# ISO_CAN_Modul.net
KiCad netlist of a schematic drawn in EAGLE
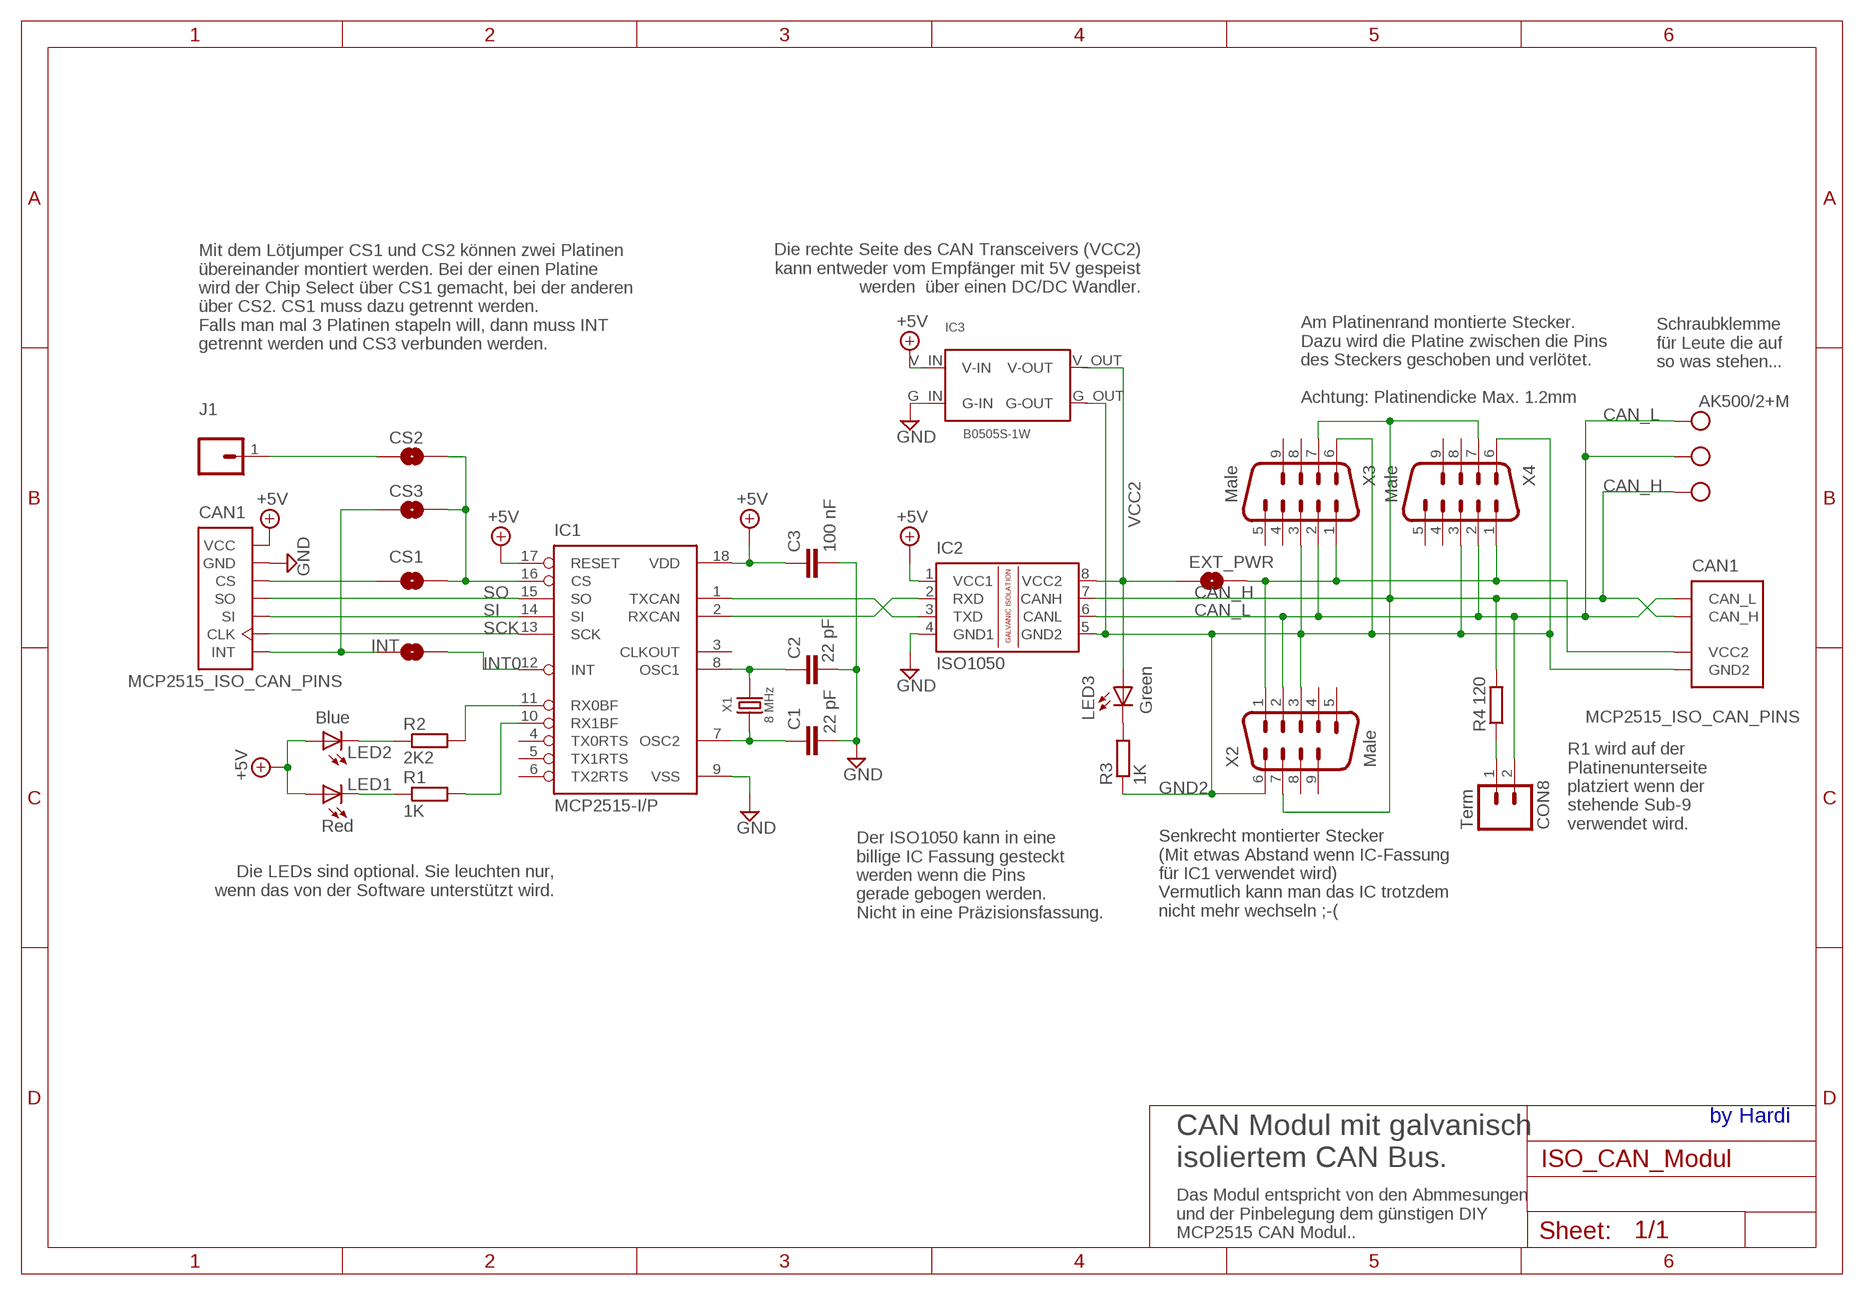
[diagram p0: schematic, sheet 1]

(export (version "E")
  (design (tool "Eeschema 10.0.6"))
  (components
    (comp (ref "C1")
      (value "22 pF")
      (footprint "eagle-import:C2.5-2")
      (libsource (lib "eagle-import") (part "C2.5/2"))
    )
    (comp (ref "C2")
      (value "22 pF")
      (footprint "eagle-import:C2.5-2")
      (libsource (lib "eagle-import") (part "C2.5/2"))
    )
    (comp (ref "C3")
      (value "100 nF")
      (footprint "eagle-import:C2.5-2")
      (libsource (lib "eagle-import") (part "C2.5/2"))
    )
    (comp (ref "CAN1")
      (value "MCP2515_ISO_CAN_PINS")
      (footprint "eagle-import:MCP2515_ISO_CAN")
      (libsource (lib "eagle-import") (part "MCP2515_ISO_CAN_PINS"))
    )
    (comp (ref "CON8")
      (value "Term")
      (footprint "eagle-import:1X02")
      (libsource (lib "eagle-import") (part "M02PTH"))
    )
    (comp (ref "CS1")
      (value "SOLDERJUMPERTRACE")
      (footprint "eagle-import:SJ_2S-TRACE")
      (libsource (lib "eagle-import") (part "SOLDERJUMPERTRACE"))
    )
    (comp (ref "CS2")
      (value "SOLDERJUMPERNO")
      (footprint "eagle-import:SJ_2S-NO")
      (libsource (lib "eagle-import") (part "SOLDERJUMPERNO"))
    )
    (comp (ref "CS3")
      (value "SOLDERJUMPERNO")
      (footprint "eagle-import:SJ_2S-NO")
      (libsource (lib "eagle-import") (part "SOLDERJUMPERNO"))
    )
    (comp (ref "EXT_PWR")
      (value "SOLDERJUMPERNO")
      (footprint "eagle-import:SJ_2S-NO")
      (libsource (lib "eagle-import") (part "SOLDERJUMPERNO"))
    )
    (comp (ref "IC1")
      (value "MCP2515-I/P")
      (footprint "eagle-import:DIL18")
      (libsource (lib "eagle-import") (part "MCP2515-I/P"))
    )
    (comp (ref "IC2")
      (value "ISO1050")
      (footprint "eagle-import:DIL08")
      (libsource (lib "eagle-import") (part "ISO1050"))
    )
    (comp (ref "IC3")
      (value "B0505S-1W")
      (footprint "eagle-import:DCDC-TEA_NME")
      (libsource (lib "eagle-import") (part "DCDC"))
    )
    (comp (ref "INT")
      (value "SOLDERJUMPERTRACE")
      (footprint "eagle-import:SJ_2S-TRACE")
      (libsource (lib "eagle-import") (part "SOLDERJUMPERTRACE"))
    )
    (comp (ref "J1")
      (value "M01")
      (footprint "eagle-import:1X01")
      (libsource (lib "eagle-import") (part "M01"))
    )
    (comp (ref "LED1")
      (value "Red")
      (footprint "eagle-import:CHIPLED_0805")
      (libsource (lib "eagle-import") (part "LEDCHIPLED_0805"))
    )
    (comp (ref "LED2")
      (value "Blue")
      (footprint "eagle-import:CHIPLED_0805")
      (libsource (lib "eagle-import") (part "LEDCHIPLED_0805"))
    )
    (comp (ref "LED3")
      (value "Green")
      (footprint "eagle-import:CHIPLED_0805")
      (libsource (lib "eagle-import") (part "LEDCHIPLED_0805"))
    )
    (comp (ref "R1")
      (value "1K")
      (footprint "eagle-import:M0805")
      (libsource (lib "eagle-import") (part "R-EU_M0805"))
    )
    (comp (ref "R2")
      (value "2K2")
      (footprint "eagle-import:M0805")
      (libsource (lib "eagle-import") (part "R-EU_M0805"))
    )
    (comp (ref "R3")
      (value "1K")
      (footprint "eagle-import:M0805")
      (libsource (lib "eagle-import") (part "R-EU_M0805"))
    )
    (comp (ref "R4")
      (value "120")
      (footprint "eagle-import:0204_7")
      (libsource (lib "eagle-import") (part "R-EU_0204/7"))
    )
    (comp (ref "X1")
      (value "8 MHz")
      (footprint "eagle-import:HC49U-V")
      (libsource (lib "eagle-import") (part "CRYSTAL-HC49U-V"))
    )
    (comp (ref "X2")
      (value "Male")
      (footprint "eagle-import:M09VB")
      (libsource (lib "eagle-import") (part "M09VB"))
    )
    (comp (ref "X3")
      (value "Male")
      (footprint "eagle-import:M09D")
      (libsource (lib "eagle-import") (part "M09D"))
    )
    (comp (ref "X4")
      (value "Male")
      (footprint "eagle-import:M09D")
      (libsource (lib "eagle-import") (part "M09D"))
    )
    (comp (ref "X5")
      (value "AK500/2+M")
      (footprint "eagle-import:AK500_2+M")
      (libsource (lib "eagle-import") (part "AK500/2+M"))
    )
  )
  (nets
    (net (code "1") (name "+5V") (class "Default")
      (node (ref "C3") (pin "1") (pinfunction "1_1") (pintype "passive"))
      (node (ref "CAN1") (pin "1") (pinfunction "VCC_1") (pintype "power_in"))
      (node (ref "IC1") (pin "17") (pinfunction "RESET_17") (pintype "input"))
      (node (ref "IC1") (pin "18") (pinfunction "VDD_18") (pintype "power_in"))
      (node (ref "IC2") (pin "1") (pinfunction "VCC1_1") (pintype "input"))
      (node (ref "IC3") (pin "V_IN") (pinfunction "V-IN_V_IN") (pintype "bidirectional"))
      (node (ref "LED1") (pin "A") (pinfunction "A_A") (pintype "passive"))
      (node (ref "LED2") (pin "A") (pinfunction "A_A") (pintype "passive"))
    )
    (net (code "2") (name "/CAN_H") (class "Default")
      (node (ref "CAN1") (pin "9") (pinfunction "CAN_H_9") (pintype "bidirectional"))
      (node (ref "IC2") (pin "7") (pinfunction "CANH_7") (pintype "input"))
      (node (ref "R4") (pin "2") (pinfunction "2_2") (pintype "passive"))
      (node (ref "X2") (pin "7") (pinfunction "7_7") (pintype "passive"))
      (node (ref "X3") (pin "7") (pinfunction "7_7") (pintype "passive"))
      (node (ref "X4") (pin "7") (pinfunction "7_7") (pintype "passive"))
      (node (ref "X5") (pin "2") (pinfunction "KL_2") (pintype "passive"))
    )
    (net (code "3") (name "/CAN_L") (class "Default")
      (node (ref "CAN1") (pin "8") (pinfunction "CAN_L_8") (pintype "bidirectional"))
      (node (ref "CON8") (pin "2") (pinfunction "2_2") (pintype "passive"))
      (node (ref "IC2") (pin "6") (pinfunction "CANL_6") (pintype "input"))
      (node (ref "X2") (pin "2") (pinfunction "2_2") (pintype "passive"))
      (node (ref "X3") (pin "2") (pinfunction "2_2") (pintype "passive"))
      (node (ref "X4") (pin "2") (pinfunction "2_2") (pintype "passive"))
      (node (ref "X5") (pin "1") (pinfunction "KL_1") (pintype "passive"))
      (node (ref "X5") (pin "M") (pinfunction "KL_M") (pintype "passive"))
    )
    (net (code "4") (name "/GND2") (class "Default")
      (node (ref "CAN1") (pin "11") (pinfunction "GND2_11") (pintype "power_in"))
      (node (ref "IC2") (pin "5") (pinfunction "GND2_5") (pintype "input"))
      (node (ref "IC3") (pin "G_OUT") (pinfunction "G-OUT_G_OUT") (pintype "bidirectional"))
      (node (ref "R3") (pin "1") (pinfunction "1_1") (pintype "passive"))
      (node (ref "X2") (pin "3") (pinfunction "3_3") (pintype "passive"))
      (node (ref "X2") (pin "6") (pinfunction "6_6") (pintype "passive"))
      (node (ref "X3") (pin "3") (pinfunction "3_3") (pintype "passive"))
      (node (ref "X3") (pin "6") (pinfunction "6_6") (pintype "passive"))
      (node (ref "X4") (pin "3") (pinfunction "3_3") (pintype "passive"))
      (node (ref "X4") (pin "6") (pinfunction "6_6") (pintype "passive"))
    )
    (net (code "5") (name "/INT0") (class "Default")
      (node (ref "IC1") (pin "12") (pinfunction "INT_12") (pintype "output"))
      (node (ref "INT") (pin "2") (pinfunction "2_2") (pintype "passive"))
    )
    (net (code "6") (name "/SCK") (class "Default")
      (node (ref "CAN1") (pin "6") (pinfunction "CLK_6") (pintype "input"))
      (node (ref "IC1") (pin "13") (pinfunction "SCK_13") (pintype "input"))
    )
    (net (code "7") (name "/SI") (class "Default")
      (node (ref "CAN1") (pin "5") (pinfunction "SI_5") (pintype "input"))
      (node (ref "IC1") (pin "14") (pinfunction "SI_14") (pintype "input"))
    )
    (net (code "8") (name "/SO") (class "Default")
      (node (ref "CAN1") (pin "4") (pinfunction "SO_4") (pintype "output"))
      (node (ref "IC1") (pin "15") (pinfunction "SO_15") (pintype "output"))
    )
    (net (code "9") (name "/VCC2") (class "Default")
      (node (ref "EXT_PWR") (pin "1") (pinfunction "1_1") (pintype "passive"))
      (node (ref "IC2") (pin "8") (pinfunction "VCC2_8") (pintype "input"))
      (node (ref "IC3") (pin "V_OUT") (pinfunction "V-OUT_V_OUT") (pintype "bidirectional"))
      (node (ref "LED3") (pin "A") (pinfunction "A_A") (pintype "passive"))
    )
    (net (code "10") (name "GND") (class "Default")
      (node (ref "C1") (pin "2") (pinfunction "2_2") (pintype "passive"))
      (node (ref "C2") (pin "2") (pinfunction "2_2") (pintype "passive"))
      (node (ref "C3") (pin "2") (pinfunction "2_2") (pintype "passive"))
      (node (ref "CAN1") (pin "2") (pinfunction "GND_2") (pintype "power_in"))
      (node (ref "IC1") (pin "9") (pinfunction "VSS_9") (pintype "power_in"))
      (node (ref "IC2") (pin "4") (pinfunction "GND1_4") (pintype "input"))
      (node (ref "IC3") (pin "G_IN") (pinfunction "G-IN_G_IN") (pintype "bidirectional"))
    )
    (net (code "11") (name "Net-(CAN1A-CS)") (class "Default")
      (node (ref "CAN1") (pin "3") (pinfunction "CS_3") (pintype "input"))
      (node (ref "CS1") (pin "1") (pinfunction "1_1") (pintype "passive"))
    )
    (net (code "12") (name "Net-(CAN1A-INT)") (class "Default")
      (node (ref "CAN1") (pin "7") (pinfunction "INT_7") (pintype "open_collector"))
      (node (ref "CS3") (pin "1") (pinfunction "1_1") (pintype "passive"))
      (node (ref "INT") (pin "1") (pinfunction "1_1") (pintype "passive"))
    )
    (net (code "13") (name "Net-(CAN1B-VCC2)") (class "Default")
      (node (ref "CAN1") (pin "10") (pinfunction "VCC2_10") (pintype "power_in"))
      (node (ref "EXT_PWR") (pin "2") (pinfunction "2_2") (pintype "passive"))
      (node (ref "X2") (pin "1") (pinfunction "1_1") (pintype "passive"))
      (node (ref "X3") (pin "1") (pinfunction "1_1") (pintype "passive"))
      (node (ref "X4") (pin "1") (pinfunction "1_1") (pintype "passive"))
    )
    (net (code "14") (name "Net-(CON8-Pad1)") (class "Default")
      (node (ref "CON8") (pin "1") (pinfunction "1_1") (pintype "passive"))
      (node (ref "R4") (pin "1") (pinfunction "1_1") (pintype "passive"))
    )
    (net (code "15") (name "Net-(CS2-Pad1)") (class "Default")
      (node (ref "CS2") (pin "1") (pinfunction "1_1") (pintype "passive"))
      (node (ref "J1") (pin "1") (pinfunction "1_1") (pintype "passive"))
    )
    (net (code "16") (name "Net-(IC1-CS)") (class "Default")
      (node (ref "CS1") (pin "2") (pinfunction "2_2") (pintype "passive"))
      (node (ref "CS2") (pin "2") (pinfunction "2_2") (pintype "passive"))
      (node (ref "CS3") (pin "2") (pinfunction "2_2") (pintype "passive"))
      (node (ref "IC1") (pin "16") (pinfunction "CS_16") (pintype "input"))
    )
    (net (code "17") (name "Net-(IC1-OSC1)") (class "Default")
      (node (ref "C2") (pin "1") (pinfunction "1_1") (pintype "passive"))
      (node (ref "IC1") (pin "8") (pinfunction "OSC1_8") (pintype "input"))
      (node (ref "X1") (pin "2") (pinfunction "2_2") (pintype "passive"))
    )
    (net (code "18") (name "Net-(IC1-OSC2)") (class "Default")
      (node (ref "C1") (pin "1") (pinfunction "1_1") (pintype "passive"))
      (node (ref "IC1") (pin "7") (pinfunction "OSC2_7") (pintype "output"))
      (node (ref "X1") (pin "1") (pinfunction "1_1") (pintype "passive"))
    )
    (net (code "19") (name "Net-(IC1-RX0BF)") (class "Default")
      (node (ref "IC1") (pin "11") (pinfunction "RX0BF_11") (pintype "output"))
      (node (ref "R2") (pin "2") (pinfunction "2_2") (pintype "passive"))
    )
    (net (code "20") (name "Net-(IC1-RX1BF)") (class "Default")
      (node (ref "IC1") (pin "10") (pinfunction "RX1BF_10") (pintype "output"))
      (node (ref "R1") (pin "2") (pinfunction "2_2") (pintype "passive"))
    )
    (net (code "21") (name "Net-(IC1-RXCAN)") (class "Default")
      (node (ref "IC1") (pin "2") (pinfunction "RXCAN_2") (pintype "input"))
      (node (ref "IC2") (pin "2") (pinfunction "RXD_2") (pintype "input"))
    )
    (net (code "22") (name "Net-(IC1-TXCAN)") (class "Default")
      (node (ref "IC1") (pin "1") (pinfunction "TXCAN_1") (pintype "output"))
      (node (ref "IC2") (pin "3") (pinfunction "TXD_3") (pintype "input"))
    )
    (net (code "23") (name "Net-(LED1-PadC)") (class "Default")
      (node (ref "LED1") (pin "C") (pinfunction "C_C") (pintype "passive"))
      (node (ref "R1") (pin "1") (pinfunction "1_1") (pintype "passive"))
    )
    (net (code "24") (name "Net-(LED2-PadC)") (class "Default")
      (node (ref "LED2") (pin "C") (pinfunction "C_C") (pintype "passive"))
      (node (ref "R2") (pin "1") (pinfunction "1_1") (pintype "passive"))
    )
    (net (code "25") (name "Net-(LED3-PadC)") (class "Default")
      (node (ref "LED3") (pin "C") (pinfunction "C_C") (pintype "passive"))
      (node (ref "R3") (pin "2") (pinfunction "2_2") (pintype "passive"))
    )
    (net (code "26") (name "unconnected-(IC1-CLKOUT-Pad3)") (class "Default")
      (node (ref "IC1") (pin "3") (pinfunction "CLKOUT_3") (pintype "output"))
    )
    (net (code "27") (name "unconnected-(IC1-TX0RTS-Pad4)") (class "Default")
      (node (ref "IC1") (pin "4") (pinfunction "TX0RTS_4") (pintype "input"))
    )
    (net (code "28") (name "unconnected-(IC1-TX1RTS-Pad5)") (class "Default")
      (node (ref "IC1") (pin "5") (pinfunction "TX1RTS_5") (pintype "input"))
    )
    (net (code "29") (name "unconnected-(IC1-TX2RTS-Pad6)") (class "Default")
      (node (ref "IC1") (pin "6") (pinfunction "TX2RTS_6") (pintype "input"))
    )
    (net (code "30") (name "unconnected-(X2-Pad4)") (class "Default")
      (node (ref "X2") (pin "4") (pinfunction "4_4") (pintype "passive"))
    )
    (net (code "31") (name "unconnected-(X2-Pad5)") (class "Default")
      (node (ref "X2") (pin "5") (pinfunction "5_5") (pintype "passive"))
    )
    (net (code "32") (name "unconnected-(X2-Pad8)") (class "Default")
      (node (ref "X2") (pin "8") (pinfunction "8_8") (pintype "passive"))
    )
    (net (code "33") (name "unconnected-(X2-Pad9)") (class "Default")
      (node (ref "X2") (pin "9") (pinfunction "9_9") (pintype "passive"))
    )
    (net (code "34") (name "unconnected-(X3-Pad4)") (class "Default")
      (node (ref "X3") (pin "4") (pinfunction "4_4") (pintype "passive"))
    )
    (net (code "35") (name "unconnected-(X3-Pad5)") (class "Default")
      (node (ref "X3") (pin "5") (pinfunction "5_5") (pintype "passive"))
    )
    (net (code "36") (name "unconnected-(X3-Pad8)") (class "Default")
      (node (ref "X3") (pin "8") (pinfunction "8_8") (pintype "passive"))
    )
    (net (code "37") (name "unconnected-(X3-Pad9)") (class "Default")
      (node (ref "X3") (pin "9") (pinfunction "9_9") (pintype "passive"))
    )
    (net (code "38") (name "unconnected-(X4-Pad4)") (class "Default")
      (node (ref "X4") (pin "4") (pinfunction "4_4") (pintype "passive"))
    )
    (net (code "39") (name "unconnected-(X4-Pad5)") (class "Default")
      (node (ref "X4") (pin "5") (pinfunction "5_5") (pintype "passive"))
    )
    (net (code "40") (name "unconnected-(X4-Pad8)") (class "Default")
      (node (ref "X4") (pin "8") (pinfunction "8_8") (pintype "passive"))
    )
    (net (code "41") (name "unconnected-(X4-Pad9)") (class "Default")
      (node (ref "X4") (pin "9") (pinfunction "9_9") (pintype "passive"))
    )
  )
)
